# 280112_Battery_Connector_UEBK-30257_1_0.net
KiCad netlist of a schematic drawn in EAGLE
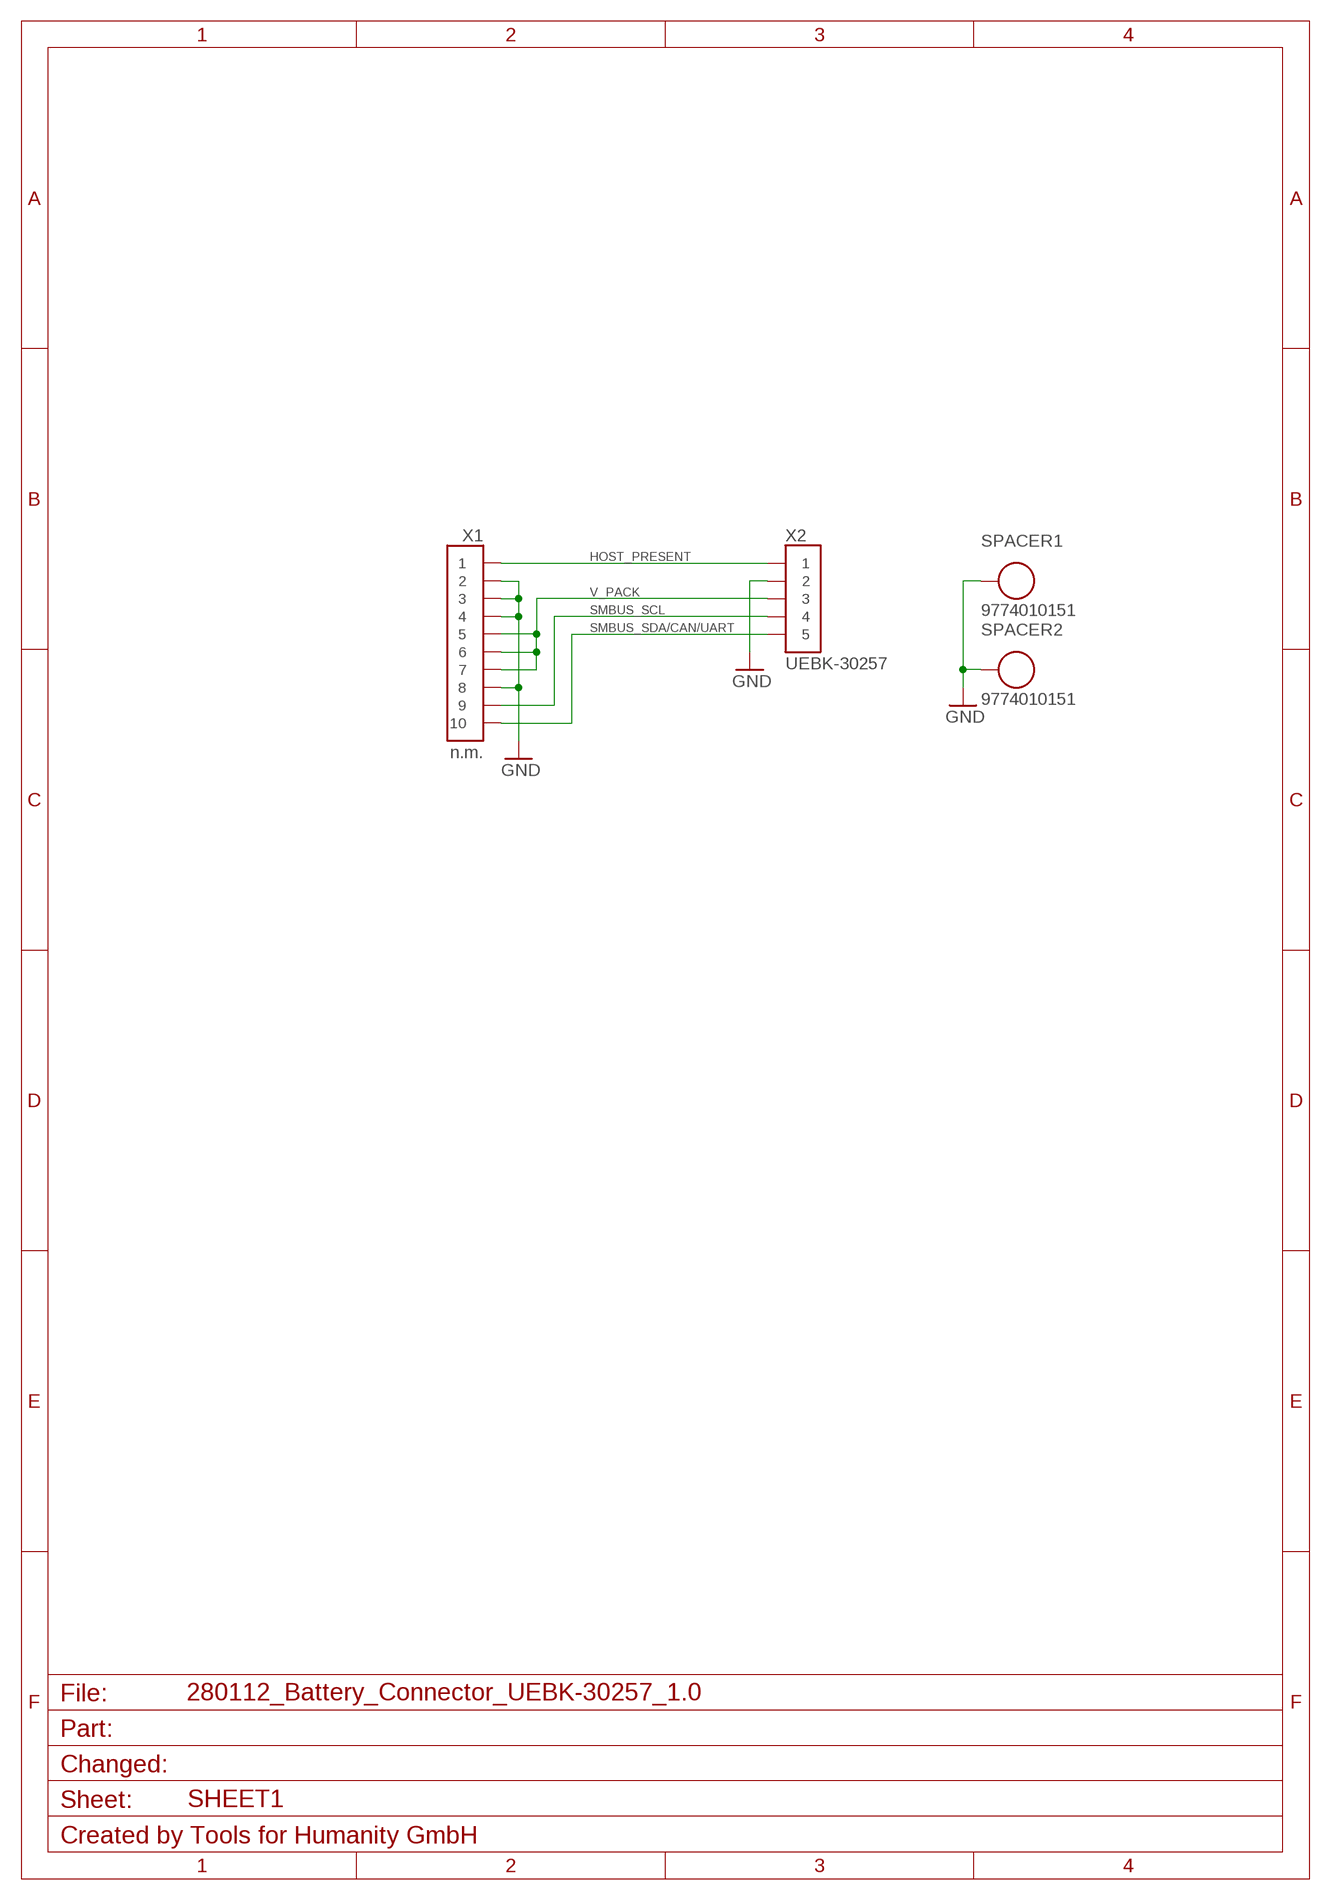
[diagram p0: schematic, sheet 1]

(export (version "E")
  (design (tool "Eeschema 10.0.6"))
  (components
    (comp (ref "SPACER1")
      (value "9774010151")
      (footprint "eagle-import:WA-SMSI_9774010151_WUERTH")
      (fields (field (name "MANUFACTURER") "Wuerth"))
      (libsource (lib "eagle-import") (part "9774010151"))
    )
    (comp (ref "SPACER2")
      (value "9774010151")
      (footprint "eagle-import:WA-SMSI_9774010151_WUERTH")
      (fields (field (name "MANUFACTURER") "Wuerth"))
      (libsource (lib "eagle-import") (part "9774010151"))
    )
    (comp (ref "X1")
      (value "n.m.")
      (footprint "eagle-import:61301011121_WUERTH")
      (fields (field (name "MANUFACTURER") "Wuerth") (field (name "VOLTAGE") "500 V(AC)"))
      (libsource (lib "eagle-import") (part "61301011121"))
    )
    (comp (ref "X2")
      (value "UEBK-30257")
      (footprint "eagle-import:UEBK-30257_UWE")
      (fields (field (name "MANUFACTURER") "uwe electronic GmbH"))
      (libsource (lib "eagle-import") (part "UEBK-30257"))
    )
  )
  (nets
    (net (code "1") (name "/HOST_PRESENT") (class "Default")
      (node (ref "X1") (pin "1") (pinfunction "1_1") (pintype "passive"))
      (node (ref "X2") (pin "1") (pinfunction "1_1") (pintype "passive"))
    )
    (net (code "2") (name "/SMBUS_SCL") (class "Default")
      (node (ref "X1") (pin "9") (pinfunction "9_9") (pintype "passive"))
      (node (ref "X2") (pin "4") (pinfunction "4_4") (pintype "passive"))
    )
    (net (code "3") (name "/SMBUS_SDA{slash}CAN{slash}UART") (class "Default")
      (node (ref "X1") (pin "10") (pinfunction "10_10") (pintype "passive"))
      (node (ref "X2") (pin "5") (pinfunction "5_5") (pintype "passive"))
    )
    (net (code "4") (name "/V_PACK") (class "Default")
      (node (ref "X1") (pin "5") (pinfunction "5_5") (pintype "passive"))
      (node (ref "X1") (pin "6") (pinfunction "6_6") (pintype "passive"))
      (node (ref "X1") (pin "7") (pinfunction "7_7") (pintype "passive"))
      (node (ref "X2") (pin "3") (pinfunction "3_3") (pintype "passive"))
    )
    (net (code "5") (name "GND") (class "Default")
      (node (ref "SPACER1") (pin "2") (pinfunction "1_2") (pintype "passive"))
      (node (ref "SPACER1") (pin "3") (pinfunction "1_3") (pintype "passive"))
      (node (ref "SPACER2") (pin "2") (pinfunction "1_2") (pintype "passive"))
      (node (ref "SPACER2") (pin "3") (pinfunction "1_3") (pintype "passive"))
      (node (ref "X1") (pin "2") (pinfunction "2_2") (pintype "passive"))
      (node (ref "X1") (pin "3") (pinfunction "3_3") (pintype "passive"))
      (node (ref "X1") (pin "4") (pinfunction "4_4") (pintype "passive"))
      (node (ref "X1") (pin "8") (pinfunction "8_8") (pintype "passive"))
      (node (ref "X2") (pin "2") (pinfunction "2_2") (pintype "passive"))
    )
  )
)
